# Power.net
KiCad netlist of a schematic drawn in Altium Designer
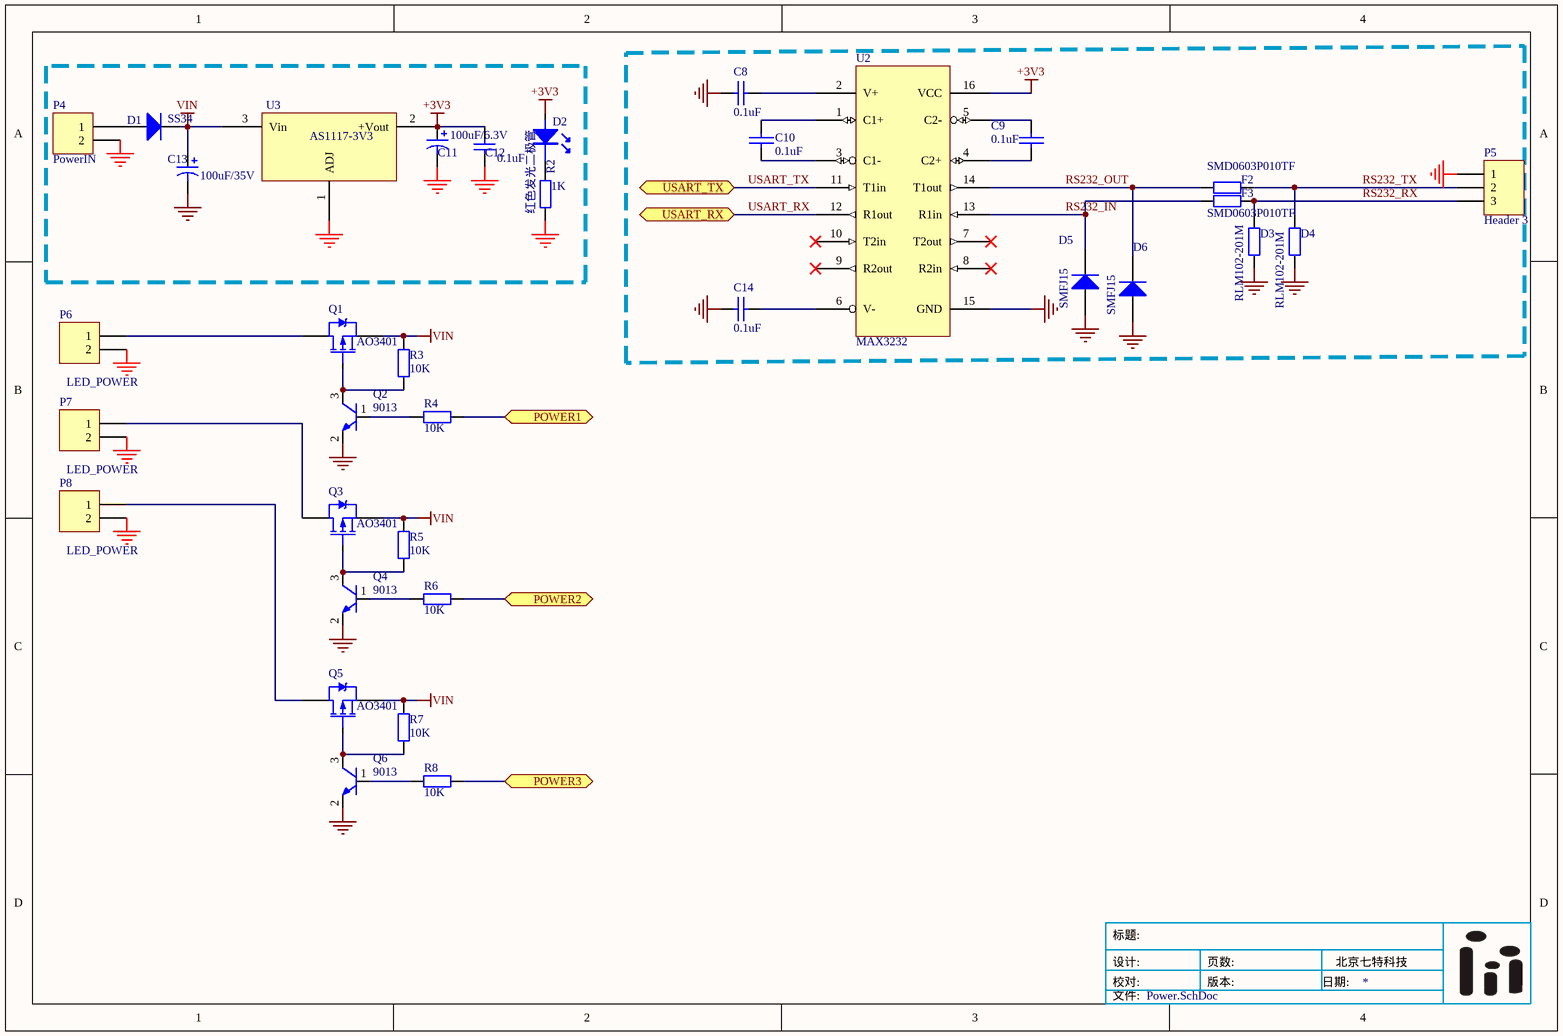
[diagram p0: Power.SchDoc]

(export (version "E")
  (design (tool "Eeschema 10.0.6"))
  (components
    (comp (ref "C8")
      (value "0.1uF")
      (footprint "C2012")
      (description "Capacitor")
      (libsource (lib "*") (part "CAP"))
    )
    (comp (ref "C9")
      (value "0.1uF")
      (footprint "C2012")
      (description "Capacitor")
      (libsource (lib "*") (part "CAP"))
    )
    (comp (ref "C10")
      (value "0.1uF")
      (footprint "C2012")
      (description "Capacitor")
      (libsource (lib "*") (part "CAP"))
    )
    (comp (ref "C11")
      (value "100uF/6.3V")
      (footprint "3216")
      (description "Polarized Capacitor (Radial)")
      (fields (field (name "PUBLISHER") "Altium Limited"))
      (libsource (lib "*") (part "Cap Pol1"))
    )
    (comp (ref "C12")
      (value "0.1uF")
      (footprint "C2012")
      (description "Capacitor")
      (fields (field (name "PUBLISHER") "Altium Limited"))
      (libsource (lib "Miscellaneous Devices") (part "Cap"))
    )
    (comp (ref "C13")
      (value "100uF/35V")
      (footprint "ECS6.3/6.6")
      (description "Polarized Capacitor (Radial)")
      (fields (field (name "PUBLISHER") "Altium Limited"))
      (libsource (lib "Miscellaneous Devices") (part "Cap Pol1"))
    )
    (comp (ref "C14")
      (value "0.1uF")
      (footprint "C2012")
      (description "Capacitor")
      (libsource (lib "*") (part "CAP"))
    )
    (comp (ref "D1")
      (value "SS34")
      (footprint "SMA_DO-214AC")
      (description "Default Diode")
      (fields (field (name "PUBLISHER") "Altium Limited"))
      (libsource (lib "*") (part "Diode"))
    )
    (comp (ref "D2") (value "红色发光二极管") (footprint "LED/S") (libsource (lib "*") (part "LED")))
    (comp (ref "D3")
      (value "RLM102-201M")
      (footprint "RLM102")
      (description "Resistor")
      (fields (field (name "PUBLISHER") "Altium Limited"))
      (libsource (lib "") (part "Res2_1"))
    )
    (comp (ref "D4")
      (value "RLM102-201M")
      (footprint "RLM102")
      (description "Resistor")
      (fields (field (name "PUBLISHER") "Altium Limited"))
      (libsource (lib "") (part "Res2_1"))
    )
    (comp (ref "D5")
      (value "SMFJ15")
      (footprint "SOD-123")
      (description "Default Diode")
      (fields (field (name "PUBLISHER") "Altium Limited"))
      (libsource (lib "*") (part "Diode"))
    )
    (comp (ref "D6")
      (value "SMFJ15")
      (footprint "SOD-123")
      (description "Default Diode")
      (fields (field (name "PUBLISHER") "Altium Limited"))
      (libsource (lib "*") (part "Diode"))
    )
    (comp (ref "F2")
      (value "SMD0603P010TF")
      (footprint "1608")
      (description "Resistor")
      (fields (field (name "PUBLISHER") "Altium Limited"))
      (libsource (lib "") (part "Res2_2"))
    )
    (comp (ref "F3")
      (value "SMD0603P010TF")
      (footprint "1608")
      (description "Resistor")
      (fields (field (name "PUBLISHER") "Altium Limited"))
      (libsource (lib "") (part "Res2_2"))
    )
    (comp (ref "P4")
      (value "PowerIN")
      (footprint "5264-2")
      (description "Header, 2-Pin")
      (fields (field (name "PUBLISHER") "Altium Limited"))
      (libsource (lib "Miscellaneous Connectors") (part "Header 2"))
    )
    (comp (ref "P5")
      (value "Header 3")
      (footprint "B3B-XH-A")
      (description "Header, 3-Pin")
      (fields (field (name "PUBLISHER") "Altium Limited"))
      (libsource (lib "Miscellaneous Connectors") (part "Header 3"))
    )
    (comp (ref "P6")
      (value "LED_POWER")
      (footprint "B2B-XH-A")
      (description "Header, 2-Pin")
      (fields (field (name "PUBLISHER") "Altium Limited"))
      (libsource (lib "Miscellaneous Connectors") (part "Header 2"))
    )
    (comp (ref "P7")
      (value "LED_POWER")
      (footprint "B2B-XH-A")
      (description "Header, 2-Pin")
      (fields (field (name "PUBLISHER") "Altium Limited"))
      (libsource (lib "Miscellaneous Connectors") (part "Header 2"))
    )
    (comp (ref "P8")
      (value "LED_POWER")
      (footprint "B2B-XH-A")
      (description "Header, 2-Pin")
      (fields (field (name "PUBLISHER") "Altium Limited"))
      (libsource (lib "Miscellaneous Connectors") (part "Header 2"))
    )
    (comp (ref "Q1")
      (value "AO3401")
      (footprint "SOT-23")
      (description "P-Channel Power MOSFET")
      (fields (field (name "PUBLISHER") "Altium Limited"))
      (libsource (lib "Miscellaneous Devices") (part "PMOS-2"))
    )
    (comp (ref "Q2") (value "9013") (footprint "sot-23") (libsource (lib "*") (part "NPNBT")))
    (comp (ref "Q3")
      (value "AO3401")
      (footprint "SOT-23")
      (description "P-Channel Power MOSFET")
      (fields (field (name "PUBLISHER") "Altium Limited"))
      (libsource (lib "Miscellaneous Devices") (part "PMOS-2"))
    )
    (comp (ref "Q4") (value "9013") (footprint "sot-23") (libsource (lib "*") (part "NPNBT")))
    (comp (ref "Q5")
      (value "AO3401")
      (footprint "SOT-23")
      (description "P-Channel Power MOSFET")
      (fields (field (name "PUBLISHER") "Altium Limited"))
      (libsource (lib "Miscellaneous Devices") (part "PMOS-2"))
    )
    (comp (ref "Q6") (value "9013") (footprint "sot-23") (libsource (lib "*") (part "NPNBT")))
    (comp (ref "R2")
      (value "1K")
      (footprint "2012")
      (description "Resistor")
      (fields (field (name "PUBLISHER") "Altium Limited"))
      (libsource (lib "") (part "Res2_1"))
    )
    (comp (ref "R3")
      (value "10K")
      (footprint "2012")
      (description "Resistor")
      (fields (field (name "PUBLISHER") "Altium Limited"))
      (libsource (lib "*") (part "Res2"))
    )
    (comp (ref "R4")
      (value "10K")
      (footprint "2012")
      (description "Resistor")
      (fields (field (name "PUBLISHER") "Altium Limited"))
      (libsource (lib "") (part "Res2_2"))
    )
    (comp (ref "R5")
      (value "10K")
      (footprint "2012")
      (description "Resistor")
      (fields (field (name "PUBLISHER") "Altium Limited"))
      (libsource (lib "*") (part "Res2"))
    )
    (comp (ref "R6")
      (value "10K")
      (footprint "2012")
      (description "Resistor")
      (fields (field (name "PUBLISHER") "Altium Limited"))
      (libsource (lib "") (part "Res2_2"))
    )
    (comp (ref "R7")
      (value "10K")
      (footprint "2012")
      (description "Resistor")
      (fields (field (name "PUBLISHER") "Altium Limited"))
      (libsource (lib "*") (part "Res2"))
    )
    (comp (ref "R8")
      (value "10K")
      (footprint "2012")
      (description "Resistor")
      (fields (field (name "PUBLISHER") "Altium Limited"))
      (libsource (lib "") (part "Res2_2"))
    )
    (comp (ref "U2")
      (value "MAX3232")
      (footprint "SO16")
      (description "3.3V/5V Dual RS232 Transceiver w/ Int. Cap.")
      (libsource (lib "*") (part "ST3232"))
    )
    (comp (ref "U3") (value "AS1117-3V3") (footprint "SOT223_L") (libsource (lib "*") (part "LM117T")))
  )
  (nets
    (net (code "1") (name "+3V3") (class "Default")
      (node (ref "C11") (pin "1") (pinfunction "1_1") (pintype "passive"))
      (node (ref "C12") (pin "2") (pinfunction "2_2") (pintype "passive"))
      (node (ref "D2") (pin "A") (pinfunction "1_A") (pintype "passive"))
      (node (ref "U2") (pin "16") (pinfunction "VCC_16") (pintype "passive"))
      (node (ref "U3") (pin "2") (pinfunction "+Vout_2") (pintype "passive"))
    )
    (net (code "2") (name "/POWER1") (class "Default")
      (node (ref "R4") (pin "1") (pinfunction "1_1") (pintype "passive"))
    )
    (net (code "3") (name "/POWER2") (class "Default")
      (node (ref "R6") (pin "1") (pinfunction "1_1") (pintype "passive"))
    )
    (net (code "4") (name "/POWER3") (class "Default")
      (node (ref "R8") (pin "1") (pinfunction "1_1") (pintype "passive"))
    )
    (net (code "5") (name "/RS232_IN") (class "Default")
      (node (ref "D5") (pin "2") (pinfunction "K_2") (pintype "passive"))
      (node (ref "F3") (pin "2") (pinfunction "2_2") (pintype "passive"))
      (node (ref "U2") (pin "13") (pinfunction "R1in_13") (pintype "input"))
    )
    (net (code "6") (name "/RS232_OUT") (class "Default")
      (node (ref "D6") (pin "2") (pinfunction "K_2") (pintype "passive"))
      (node (ref "F2") (pin "2") (pinfunction "2_2") (pintype "passive"))
      (node (ref "U2") (pin "14") (pinfunction "T1out_14") (pintype "output"))
    )
    (net (code "7") (name "/RS232_RX") (class "Default")
      (node (ref "D3") (pin "1") (pinfunction "1_1") (pintype "passive"))
      (node (ref "F3") (pin "1") (pinfunction "1_1") (pintype "passive"))
      (node (ref "P5") (pin "3") (pinfunction "3_3") (pintype "passive"))
    )
    (net (code "8") (name "/RS232_TX") (class "Default")
      (node (ref "D4") (pin "1") (pinfunction "1_1") (pintype "passive"))
      (node (ref "F2") (pin "1") (pinfunction "1_1") (pintype "passive"))
      (node (ref "P5") (pin "2") (pinfunction "2_2") (pintype "passive"))
    )
    (net (code "9") (name "/USART_RX") (class "Default")
      (node (ref "U2") (pin "12") (pinfunction "R1out_12") (pintype "output"))
    )
    (net (code "10") (name "/USART_TX") (class "Default")
      (node (ref "U2") (pin "11") (pinfunction "T1in_11") (pintype "input"))
    )
    (net (code "11") (name "GND") (class "Default")
      (node (ref "C11") (pin "2") (pinfunction "2_2") (pintype "passive"))
      (node (ref "C12") (pin "1") (pinfunction "1_1") (pintype "passive"))
      (node (ref "C13") (pin "2") (pinfunction "2_2") (pintype "passive"))
      (node (ref "C14") (pin "2") (pinfunction "2_2") (pintype "passive"))
      (node (ref "C8") (pin "1") (pinfunction "1_1") (pintype "passive"))
      (node (ref "D3") (pin "2") (pinfunction "2_2") (pintype "passive"))
      (node (ref "D4") (pin "2") (pinfunction "2_2") (pintype "passive"))
      (node (ref "D5") (pin "1") (pinfunction "A_1") (pintype "passive"))
      (node (ref "D6") (pin "1") (pinfunction "A_1") (pintype "passive"))
      (node (ref "P4") (pin "2") (pinfunction "2_2") (pintype "passive"))
      (node (ref "P5") (pin "1") (pinfunction "1_1") (pintype "passive"))
      (node (ref "P6") (pin "2") (pinfunction "2_2") (pintype "passive"))
      (node (ref "P7") (pin "2") (pinfunction "2_2") (pintype "passive"))
      (node (ref "P8") (pin "2") (pinfunction "2_2") (pintype "passive"))
      (node (ref "Q2") (pin "2") (pinfunction "E_2") (pintype "passive"))
      (node (ref "Q4") (pin "2") (pinfunction "E_2") (pintype "passive"))
      (node (ref "Q6") (pin "2") (pinfunction "E_2") (pintype "passive"))
      (node (ref "R2") (pin "2") (pinfunction "2_2") (pintype "passive"))
      (node (ref "U2") (pin "15") (pinfunction "GND_15") (pintype "passive"))
      (node (ref "U3") (pin "1") (pinfunction "ADJ_1") (pintype "passive"))
    )
    (net (code "12") (name "Net-(D1-A)") (class "Default")
      (node (ref "D1") (pin "1") (pinfunction "A_1") (pintype "passive"))
      (node (ref "P4") (pin "1") (pinfunction "1_1") (pintype "passive"))
    )
    (net (code "13") (name "Net-(D2-2)") (class "Default")
      (node (ref "D2") (pin "K") (pinfunction "2_K") (pintype "passive"))
      (node (ref "R2") (pin "1") (pinfunction "1_1") (pintype "passive"))
    )
    (net (code "14") (name "Net-(Q1-G)") (class "Default")
      (node (ref "Q1") (pin "1") (pinfunction "G_1") (pintype "passive"))
      (node (ref "Q2") (pin "3") (pinfunction "C_3") (pintype "passive"))
      (node (ref "R3") (pin "1") (pinfunction "1_1") (pintype "passive"))
    )
    (net (code "15") (name "Net-(Q1-S)") (class "Default")
      (node (ref "P6") (pin "1") (pinfunction "1_1") (pintype "passive"))
      (node (ref "Q1") (pin "3") (pinfunction "S_3") (pintype "passive"))
    )
    (net (code "16") (name "Net-(Q2-B)") (class "Default")
      (node (ref "Q2") (pin "1") (pinfunction "B_1") (pintype "passive"))
      (node (ref "R4") (pin "2") (pinfunction "2_2") (pintype "passive"))
    )
    (net (code "17") (name "Net-(Q3-G)") (class "Default")
      (node (ref "Q3") (pin "1") (pinfunction "G_1") (pintype "passive"))
      (node (ref "Q4") (pin "3") (pinfunction "C_3") (pintype "passive"))
      (node (ref "R5") (pin "1") (pinfunction "1_1") (pintype "passive"))
    )
    (net (code "18") (name "Net-(Q3-S)") (class "Default")
      (node (ref "P7") (pin "1") (pinfunction "1_1") (pintype "passive"))
      (node (ref "Q3") (pin "3") (pinfunction "S_3") (pintype "passive"))
    )
    (net (code "19") (name "Net-(Q4-B)") (class "Default")
      (node (ref "Q4") (pin "1") (pinfunction "B_1") (pintype "passive"))
      (node (ref "R6") (pin "2") (pinfunction "2_2") (pintype "passive"))
    )
    (net (code "20") (name "Net-(Q5-G)") (class "Default")
      (node (ref "Q5") (pin "1") (pinfunction "G_1") (pintype "passive"))
      (node (ref "Q6") (pin "3") (pinfunction "C_3") (pintype "passive"))
      (node (ref "R7") (pin "1") (pinfunction "1_1") (pintype "passive"))
    )
    (net (code "21") (name "Net-(Q5-S)") (class "Default")
      (node (ref "P8") (pin "1") (pinfunction "1_1") (pintype "passive"))
      (node (ref "Q5") (pin "3") (pinfunction "S_3") (pintype "passive"))
    )
    (net (code "22") (name "Net-(Q6-B)") (class "Default")
      (node (ref "Q6") (pin "1") (pinfunction "B_1") (pintype "passive"))
      (node (ref "R8") (pin "2") (pinfunction "2_2") (pintype "passive"))
    )
    (net (code "23") (name "Net-(U2-C1+)") (class "Default")
      (node (ref "C10") (pin "1") (pinfunction "1_1") (pintype "passive"))
      (node (ref "U2") (pin "1") (pinfunction "C1+_1") (pintype "bidirectional"))
    )
    (net (code "24") (name "Net-(U2-C1-)") (class "Default")
      (node (ref "C10") (pin "2") (pinfunction "2_2") (pintype "passive"))
      (node (ref "U2") (pin "3") (pinfunction "C1-_3") (pintype "bidirectional"))
    )
    (net (code "25") (name "Net-(U2-C2+)") (class "Default")
      (node (ref "C9") (pin "1") (pinfunction "1_1") (pintype "passive"))
      (node (ref "U2") (pin "4") (pinfunction "C2+_4") (pintype "bidirectional"))
    )
    (net (code "26") (name "Net-(U2-C2-)") (class "Default")
      (node (ref "C9") (pin "2") (pinfunction "2_2") (pintype "passive"))
      (node (ref "U2") (pin "5") (pinfunction "C2-_5") (pintype "bidirectional"))
    )
    (net (code "27") (name "Net-(U2-V+)") (class "Default")
      (node (ref "C8") (pin "2") (pinfunction "2_2") (pintype "passive"))
      (node (ref "U2") (pin "2") (pinfunction "V+_2") (pintype "passive"))
    )
    (net (code "28") (name "Net-(U2-V-)") (class "Default")
      (node (ref "C14") (pin "1") (pinfunction "1_1") (pintype "passive"))
      (node (ref "U2") (pin "6") (pinfunction "V-_6") (pintype "passive"))
    )
    (net (code "29") (name "VIN") (class "Default")
      (node (ref "C13") (pin "1") (pinfunction "1_1") (pintype "passive"))
      (node (ref "D1") (pin "2") (pinfunction "K_2") (pintype "passive"))
      (node (ref "Q1") (pin "2") (pinfunction "D_2") (pintype "passive"))
      (node (ref "Q3") (pin "2") (pinfunction "D_2") (pintype "passive"))
      (node (ref "Q5") (pin "2") (pinfunction "D_2") (pintype "passive"))
      (node (ref "R3") (pin "2") (pinfunction "2_2") (pintype "passive"))
      (node (ref "R5") (pin "2") (pinfunction "2_2") (pintype "passive"))
      (node (ref "R7") (pin "2") (pinfunction "2_2") (pintype "passive"))
      (node (ref "U3") (pin "3") (pinfunction "Vin_3") (pintype "passive"))
    )
    (net (code "30") (name "unconnected-(U2-R2in-Pad8)") (class "Default")
      (node (ref "U2") (pin "8") (pinfunction "R2in_8") (pintype "input+no_connect"))
    )
    (net (code "31") (name "unconnected-(U2-R2out-Pad9)") (class "Default")
      (node (ref "U2") (pin "9") (pinfunction "R2out_9") (pintype "output+no_connect"))
    )
    (net (code "32") (name "unconnected-(U2-T2in-Pad10)") (class "Default")
      (node (ref "U2") (pin "10") (pinfunction "T2in_10") (pintype "input+no_connect"))
    )
    (net (code "33") (name "unconnected-(U2-T2out-Pad7)") (class "Default")
      (node (ref "U2") (pin "7") (pinfunction "T2out_7") (pintype "output+no_connect"))
    )
  )
)
